# ESQUEMATICO.net
KiCad netlist of a schematic drawn in Altium Designer
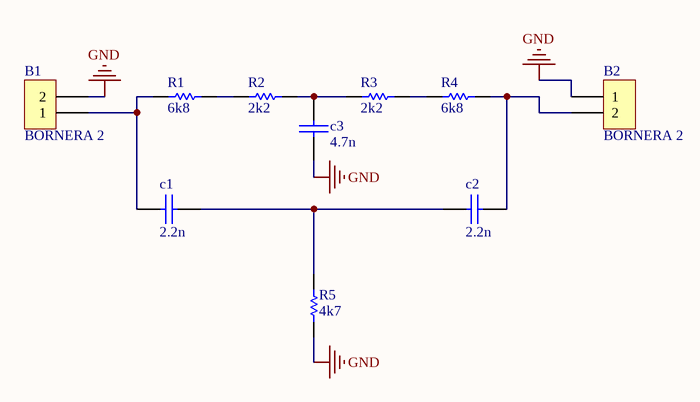
[diagram p0: ESQUEMATICO.SchDoc]

(export (version "E")
  (design (tool "Eeschema 10.0.6"))
  (components
    (comp (ref "B1")
      (value "BORNERA 2")
      (footprint "BORNERA2")
      (libsource (lib "LIBEBAL") (part "BORNERA 2"))
    )
    (comp (ref "B2") (value "BORNERA 2") (footprint "BORNERA2") (libsource (lib "") (part "BORNERA 2_1")))
    (comp (ref "c1") (value "2.2n") (footprint "CAP200") (libsource (lib "LIBEBAL") (part "CAP")))
    (comp (ref "c2") (value "2.2n") (footprint "CAP200") (libsource (lib "LIBEBAL") (part "CAP")))
    (comp (ref "c3") (value "4.7n") (footprint "CAP200") (libsource (lib "LIBEBAL") (part "CAP")))
    (comp (ref "R1") (value "6k8") (footprint "RES400") (libsource (lib "LIBEBAL") (part "RES")))
    (comp (ref "R2") (value "2k2") (footprint "RES400") (libsource (lib "LIBEBAL") (part "RES")))
    (comp (ref "R3") (value "2k2") (footprint "RES400") (libsource (lib "LIBEBAL") (part "RES")))
    (comp (ref "R4") (value "6k8") (footprint "RES400") (libsource (lib "LIBEBAL") (part "RES")))
    (comp (ref "R5") (value "4k7") (footprint "RES400") (libsource (lib "LIBEBAL") (part "RES")))
  )
  (nets
    (net (code "1") (name "GND") (class "Default")
      (node (ref "B1") (pin "2") (pinfunction "2_2") (pintype "passive"))
      (node (ref "B2") (pin "1") (pinfunction "1_1") (pintype "passive"))
      (node (ref "R5") (pin "1") (pinfunction "1_1") (pintype "passive"))
      (node (ref "c3") (pin "2") (pinfunction "2_2") (pintype "passive"))
    )
    (net (code "2") (name "Net-(B1-Pad1)") (class "Default")
      (node (ref "B1") (pin "1") (pinfunction "1_1") (pintype "passive"))
      (node (ref "R1") (pin "1") (pinfunction "1_1") (pintype "passive"))
      (node (ref "c1") (pin "1") (pinfunction "1_1") (pintype "passive"))
    )
    (net (code "3") (name "Net-(B2-Pad2)") (class "Default")
      (node (ref "B2") (pin "2") (pinfunction "2_2") (pintype "passive"))
      (node (ref "R4") (pin "2") (pinfunction "2_2") (pintype "passive"))
      (node (ref "c2") (pin "2") (pinfunction "2_2") (pintype "passive"))
    )
    (net (code "4") (name "Net-(R1-Pad2)") (class "Default")
      (node (ref "R1") (pin "2") (pinfunction "2_2") (pintype "passive"))
      (node (ref "R2") (pin "1") (pinfunction "1_1") (pintype "passive"))
    )
    (net (code "5") (name "Net-(R2-Pad2)") (class "Default")
      (node (ref "R2") (pin "2") (pinfunction "2_2") (pintype "passive"))
      (node (ref "R3") (pin "1") (pinfunction "1_1") (pintype "passive"))
      (node (ref "c3") (pin "1") (pinfunction "1_1") (pintype "passive"))
    )
    (net (code "6") (name "Net-(R3-Pad2)") (class "Default")
      (node (ref "R3") (pin "2") (pinfunction "2_2") (pintype "passive"))
      (node (ref "R4") (pin "1") (pinfunction "1_1") (pintype "passive"))
    )
    (net (code "7") (name "Net-(R5-Pad2)") (class "Default")
      (node (ref "R5") (pin "2") (pinfunction "2_2") (pintype "passive"))
      (node (ref "c1") (pin "2") (pinfunction "2_2") (pintype "passive"))
      (node (ref "c2") (pin "1") (pinfunction "1_1") (pintype "passive"))
    )
  )
)
